# memristor_measure_sch.net
KiCad netlist of a schematic drawn in Altium Designer
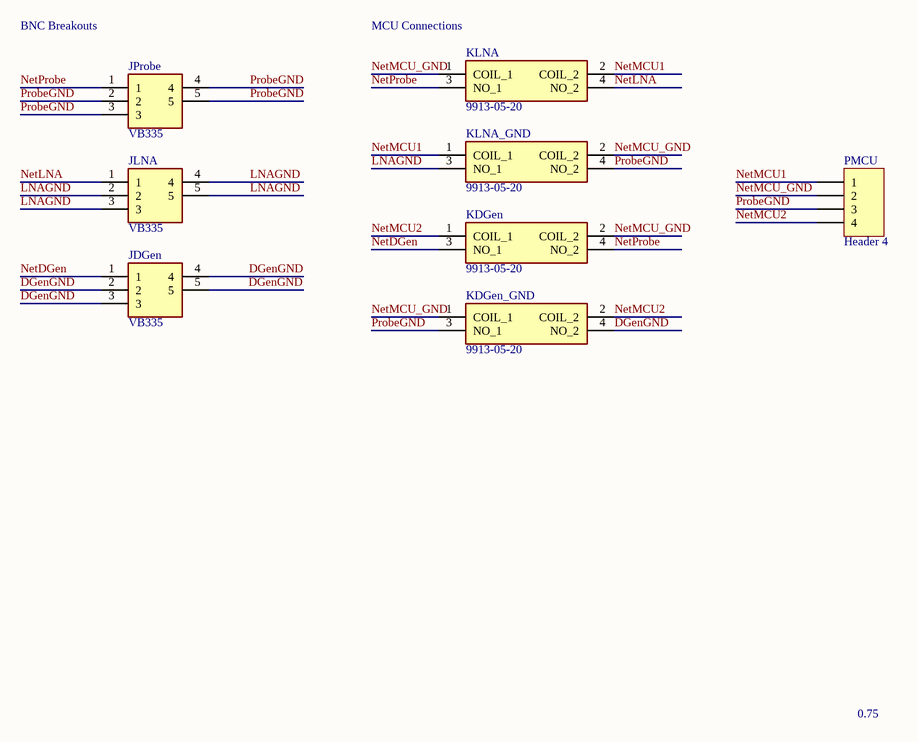
[diagram p0: memristor_measure_sch.SchDoc]

(export (version "E")
  (design (tool "Eeschema 10.0.6"))
  (components
    (comp (ref "JDGen")
      (value "VB335")
      (footprint "SamacSys:VB335")
      (description "Connector")
      (libsource (lib "*") (part "VB335"))
    )
    (comp (ref "JLNA")
      (value "VB335")
      (footprint "SamacSys:VB335")
      (description "Connector")
      (libsource (lib "*") (part "VB335"))
    )
    (comp (ref "JProbe")
      (value "VB335")
      (footprint "SamacSys:VB335")
      (description "Connector")
      (libsource (lib "*") (part "VB335"))
    )
    (comp (ref "KDGen")
      (value "9913-05-20")
      (footprint "SamacSys:99130520")
      (description "Relay or Contactor")
      (libsource (lib "*") (part "9913-05-20"))
    )
    (comp (ref "KDGen_GND")
      (value "9913-05-20")
      (footprint "SamacSys:99130520")
      (description "Relay or Contactor")
      (libsource (lib "*") (part "9913-05-20"))
    )
    (comp (ref "KLNA")
      (value "9913-05-20")
      (footprint "SamacSys:99130520")
      (description "Relay or Contactor")
      (libsource (lib "*") (part "9913-05-20"))
    )
    (comp (ref "KLNA_GND")
      (value "9913-05-20")
      (footprint "SamacSys:99130520")
      (description "Relay or Contactor")
      (libsource (lib "*") (part "9913-05-20"))
    )
    (comp (ref "PMCU")
      (value "Header 4")
      (footprint "HDR1X4")
      (description "Header, 4-Pin")
      (fields (field (name "PUBLISHER") "Altium Limited"))
      (libsource (lib "Miscellaneous Connectors") (part "Header 4"))
    )
  )
  (nets
    (net (code "1") (name "/DGenGND") (class "Default")
      (node (ref "JDGen") (pin "2") (pinfunction "2_2") (pintype "passive"))
      (node (ref "JDGen") (pin "3") (pinfunction "3_3") (pintype "passive"))
      (node (ref "JDGen") (pin "4") (pinfunction "4_4") (pintype "passive"))
      (node (ref "JDGen") (pin "5") (pinfunction "5_5") (pintype "passive"))
      (node (ref "KDGen_GND") (pin "4") (pinfunction "NO_2_4") (pintype "passive"))
    )
    (net (code "2") (name "/LNAGND") (class "Default")
      (node (ref "JLNA") (pin "2") (pinfunction "2_2") (pintype "passive"))
      (node (ref "JLNA") (pin "3") (pinfunction "3_3") (pintype "passive"))
      (node (ref "JLNA") (pin "4") (pinfunction "4_4") (pintype "passive"))
      (node (ref "JLNA") (pin "5") (pinfunction "5_5") (pintype "passive"))
      (node (ref "KLNA_GND") (pin "3") (pinfunction "NO_1_3") (pintype "passive"))
    )
    (net (code "3") (name "/NetDGen") (class "Default")
      (node (ref "JDGen") (pin "1") (pinfunction "1_1") (pintype "passive"))
      (node (ref "KDGen") (pin "3") (pinfunction "NO_1_3") (pintype "passive"))
    )
    (net (code "4") (name "/NetLNA") (class "Default")
      (node (ref "JLNA") (pin "1") (pinfunction "1_1") (pintype "passive"))
      (node (ref "KLNA") (pin "4") (pinfunction "NO_2_4") (pintype "passive"))
    )
    (net (code "5") (name "/NetMCU1") (class "Default")
      (node (ref "KLNA") (pin "2") (pinfunction "COIL_2_2") (pintype "passive"))
      (node (ref "KLNA_GND") (pin "1") (pinfunction "COIL_1_1") (pintype "passive"))
      (node (ref "PMCU") (pin "1") (pinfunction "1_1") (pintype "passive"))
    )
    (net (code "6") (name "/NetMCU2") (class "Default")
      (node (ref "KDGen") (pin "1") (pinfunction "COIL_1_1") (pintype "passive"))
      (node (ref "KDGen_GND") (pin "2") (pinfunction "COIL_2_2") (pintype "passive"))
      (node (ref "PMCU") (pin "4") (pinfunction "4_4") (pintype "passive"))
    )
    (net (code "7") (name "/NetMCU_GND") (class "Default")
      (node (ref "KDGen") (pin "2") (pinfunction "COIL_2_2") (pintype "passive"))
      (node (ref "KDGen_GND") (pin "1") (pinfunction "COIL_1_1") (pintype "passive"))
      (node (ref "KLNA") (pin "1") (pinfunction "COIL_1_1") (pintype "passive"))
      (node (ref "KLNA_GND") (pin "2") (pinfunction "COIL_2_2") (pintype "passive"))
      (node (ref "PMCU") (pin "2") (pinfunction "2_2") (pintype "passive"))
    )
    (net (code "8") (name "/NetProbe") (class "Default")
      (node (ref "JProbe") (pin "1") (pinfunction "1_1") (pintype "passive"))
      (node (ref "KDGen") (pin "4") (pinfunction "NO_2_4") (pintype "passive"))
      (node (ref "KLNA") (pin "3") (pinfunction "NO_1_3") (pintype "passive"))
    )
    (net (code "9") (name "/ProbeGND") (class "Default")
      (node (ref "JProbe") (pin "2") (pinfunction "2_2") (pintype "passive"))
      (node (ref "JProbe") (pin "3") (pinfunction "3_3") (pintype "passive"))
      (node (ref "JProbe") (pin "4") (pinfunction "4_4") (pintype "passive"))
      (node (ref "JProbe") (pin "5") (pinfunction "5_5") (pintype "passive"))
      (node (ref "KDGen_GND") (pin "3") (pinfunction "NO_1_3") (pintype "passive"))
      (node (ref "KLNA_GND") (pin "4") (pinfunction "NO_2_4") (pintype "passive"))
      (node (ref "PMCU") (pin "3") (pinfunction "3_3") (pintype "passive"))
    )
  )
)
